# Grove_I2C_FM_Receiver_v1_0.net
KiCad netlist of a schematic drawn in EAGLE
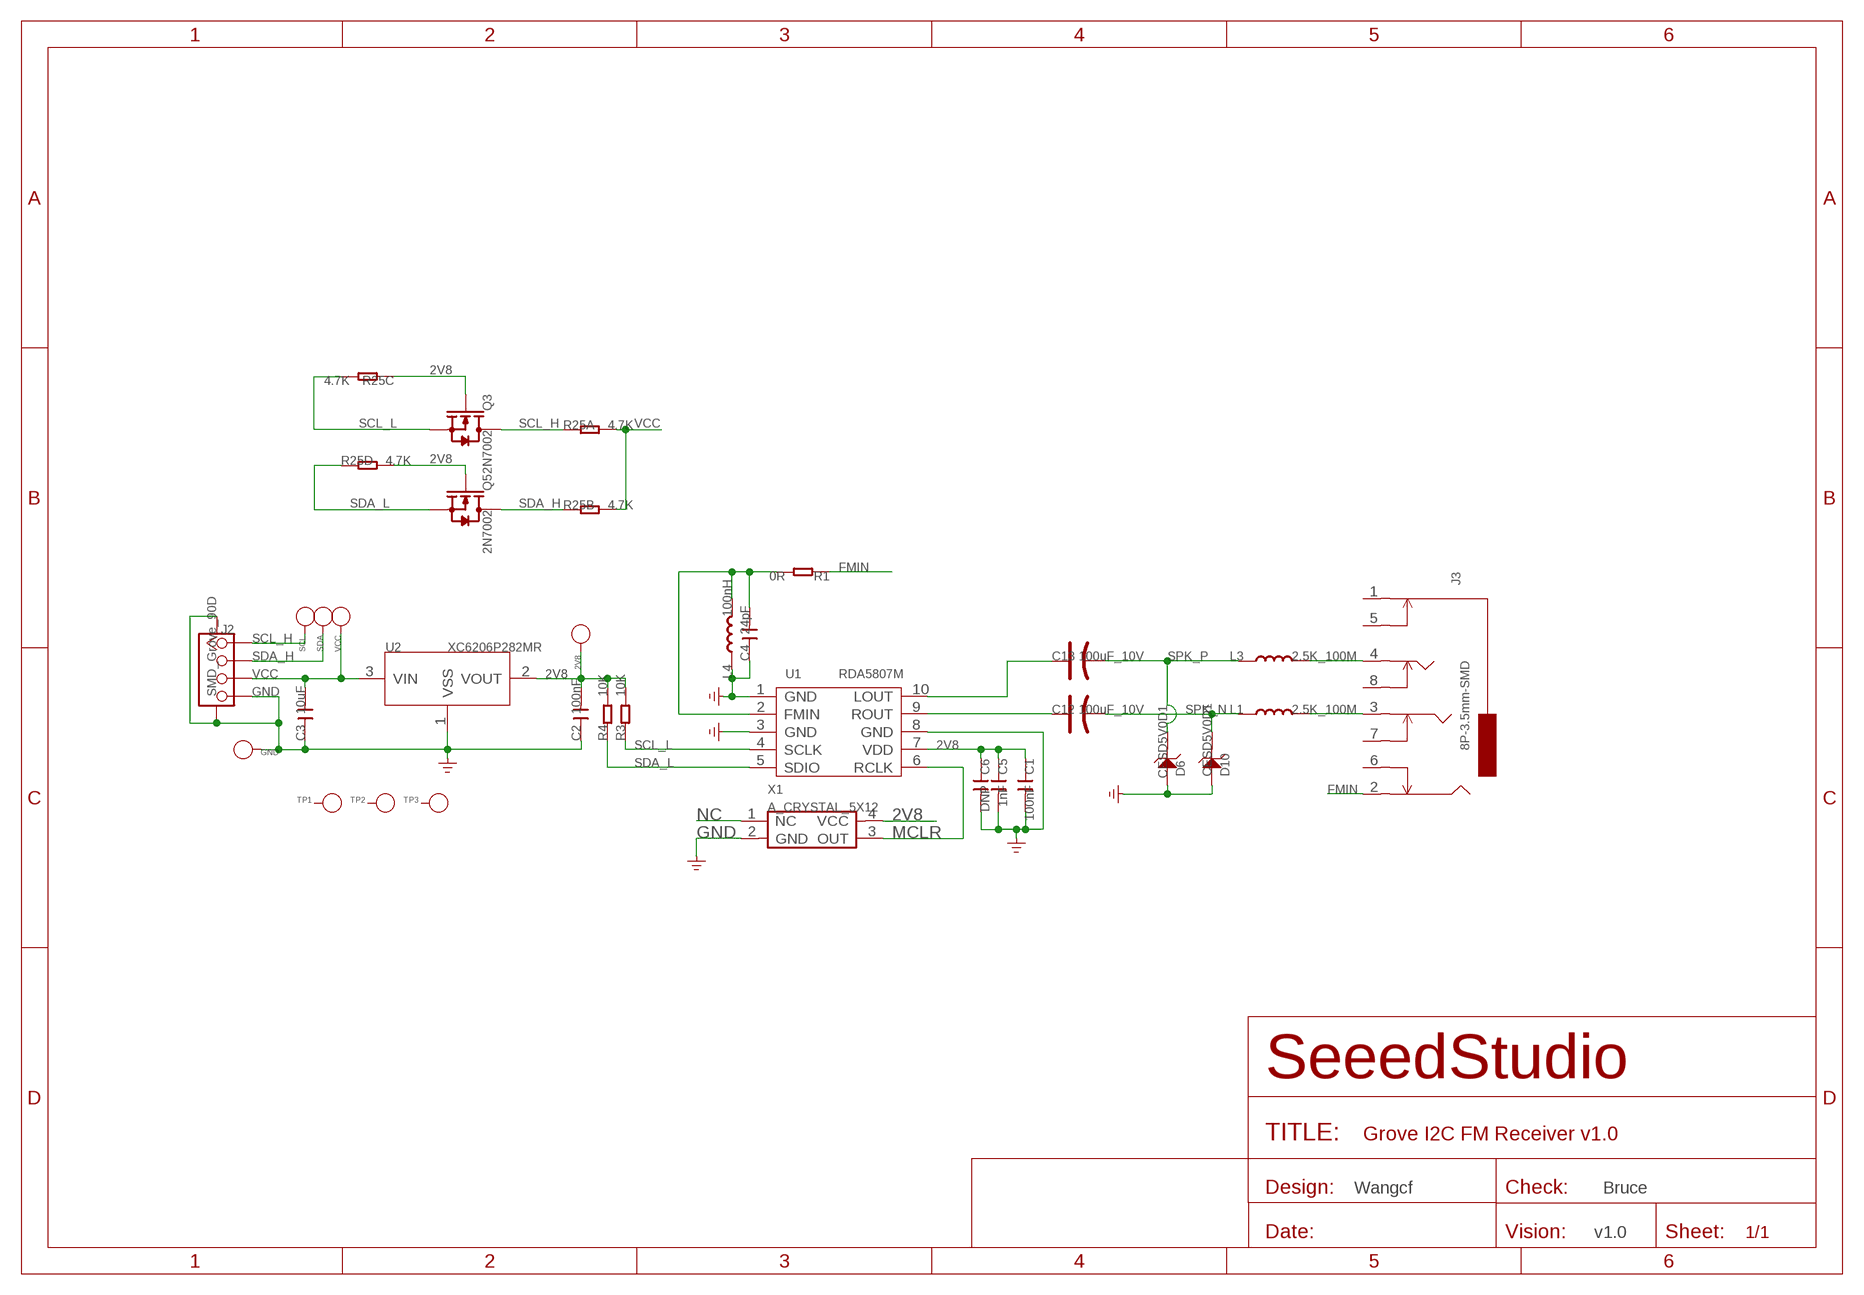
[diagram p0: schematic, sheet 1]

(export (version "E")
  (design (tool "Eeschema 10.0.6"))
  (components
    (comp (ref "2V8")
      (value "PAD-TEST-POINT'4545'")
      (footprint "eagle-import:TP_4545")
      (fields (field (name "PARTNO") "DNP"))
      (libsource (lib "eagle-import") (part "PAD-TEST-POINT'4545'"))
    )
    (comp (ref "C1")
      (value "100nF")
      (footprint "eagle-import:C0603")
      (libsource (lib "eagle-import") (part "C-0603"))
    )
    (comp (ref "C2")
      (value "100nF")
      (footprint "eagle-import:C0603")
      (libsource (lib "eagle-import") (part "C-0603"))
    )
    (comp (ref "C3")
      (value "10uF")
      (footprint "eagle-import:C0805")
      (libsource (lib "eagle-import") (part "C-0805"))
    )
    (comp (ref "C4")
      (value "24pF")
      (footprint "eagle-import:C0603")
      (libsource (lib "eagle-import") (part "C-0603"))
    )
    (comp (ref "C5")
      (value "1nF")
      (footprint "eagle-import:C0603")
      (libsource (lib "eagle-import") (part "C-0603"))
    )
    (comp (ref "C6")
      (value "DNP")
      (footprint "eagle-import:C0603")
      (libsource (lib "eagle-import") (part "C-0603"))
    )
    (comp (ref "C12")
      (value "100uF_10V")
      (footprint "eagle-import:AVX-B")
      (libsource (lib "eagle-import") (part "CAP-AVX-B"))
    )
    (comp (ref "C13")
      (value "100uF_10V")
      (footprint "eagle-import:AVX-B")
      (libsource (lib "eagle-import") (part "CAP-AVX-B"))
    )
    (comp (ref "D6")
      (value "CESD5V0D1")
      (footprint "eagle-import:SOD123-2.7X1.6")
      (libsource (lib "eagle-import") (part "D-ESD"))
    )
    (comp (ref "D10")
      (value "CESD5V0D1")
      (footprint "eagle-import:SOD123-2.7X1.6")
      (libsource (lib "eagle-import") (part "D-ESD"))
    )
    (comp (ref "GND")
      (value "PAD-TEST-POINT'4545'")
      (footprint "eagle-import:TP_4545")
      (fields (field (name "PARTNO") "DNP"))
      (libsource (lib "eagle-import") (part "PAD-TEST-POINT'4545'"))
    )
    (comp (ref "J2")
      (value "SMD_Grove_90D")
      (footprint "eagle-import:4P-SMD-2.0")
      (libsource (lib "eagle-import") (part "TWIG-4P-2.0-SMD-FEMALE-REINFORCE'DD'"))
    )
    (comp (ref "J3")
      (value "8P-3.5mm-SMD")
      (footprint "eagle-import:8P-3.5-SMD")
      (libsource (lib "eagle-import") (part "AUDIO-8P'PJ-3536-L6S'"))
    )
    (comp (ref "L1")
      (value "2.5K_100M")
      (footprint "eagle-import:L0603")
      (libsource (lib "eagle-import") (part "L'0603'"))
    )
    (comp (ref "L3")
      (value "2.5K_100M")
      (footprint "eagle-import:L0603")
      (libsource (lib "eagle-import") (part "L'0603'"))
    )
    (comp (ref "L4")
      (value "100nH")
      (footprint "eagle-import:L0603")
      (libsource (lib "eagle-import") (part "L'0603'"))
    )
    (comp (ref "Q3")
      (value "2N7002")
      (footprint "eagle-import:SOT23")
      (libsource (lib "eagle-import") (part "MOSFET-N'SOT23'"))
    )
    (comp (ref "Q5")
      (value "2N7002")
      (footprint "eagle-import:SOT23")
      (libsource (lib "eagle-import") (part "MOSFET-N'SOT23'"))
    )
    (comp (ref "R1")
      (value "0R")
      (footprint "eagle-import:R0603")
      (libsource (lib "eagle-import") (part "R-0603"))
    )
    (comp (ref "R3")
      (value "10K")
      (footprint "eagle-import:R0603")
      (libsource (lib "eagle-import") (part "R-0603"))
    )
    (comp (ref "R4")
      (value "10K")
      (footprint "eagle-import:R0603")
      (libsource (lib "eagle-import") (part "R-0603"))
    )
    (comp (ref "R25")
      (value "4.7K")
      (footprint "eagle-import:1206-8-3.3X2.4")
      (libsource (lib "eagle-import") (part "R-4R-1206"))
    )
    (comp (ref "SCL")
      (value "PAD-TEST-POINT'4545'")
      (footprint "eagle-import:TP_4545")
      (fields (field (name "PARTNO") "DNP"))
      (libsource (lib "eagle-import") (part "PAD-TEST-POINT'4545'"))
    )
    (comp (ref "SDA")
      (value "PAD-TEST-POINT'4545'")
      (footprint "eagle-import:TP_4545")
      (fields (field (name "PARTNO") "DNP"))
      (libsource (lib "eagle-import") (part "PAD-TEST-POINT'4545'"))
    )
    (comp (ref "TP1")
      (value "PAD-TEST-POINT'4545'")
      (footprint "eagle-import:TP_4545")
      (fields (field (name "PARTNO") "DNP"))
      (libsource (lib "eagle-import") (part "PAD-TEST-POINT'4545'"))
    )
    (comp (ref "TP2")
      (value "PAD-TEST-POINT'4545'")
      (footprint "eagle-import:TP_4545")
      (fields (field (name "PARTNO") "DNP"))
      (libsource (lib "eagle-import") (part "PAD-TEST-POINT'4545'"))
    )
    (comp (ref "TP3")
      (value "PAD-TEST-POINT'4545'")
      (footprint "eagle-import:TP_4545")
      (fields (field (name "PARTNO") "DNP"))
      (libsource (lib "eagle-import") (part "PAD-TEST-POINT'4545'"))
    )
    (comp (ref "U1")
      (value "RDA5807M")
      (footprint "eagle-import:MSOP10")
      (libsource (lib "eagle-import") (part "RDA5807M"))
    )
    (comp (ref "U2")
      (value "XC6206P282MR")
      (footprint "eagle-import:SOT23")
      (libsource (lib "eagle-import") (part "XC6206MR"))
    )
    (comp (ref "VCC")
      (value "PAD-TEST-POINT'4545'")
      (footprint "eagle-import:TP_4545")
      (fields (field (name "PARTNO") "DNP"))
      (libsource (lib "eagle-import") (part "PAD-TEST-POINT'4545'"))
    )
    (comp (ref "X1")
      (value "A_CRYSTAL_5X12")
      (footprint "eagle-import:4P_5X12")
      (libsource (lib "eagle-import") (part "A_CRYSTAL_5X12"))
    )
  )
  (nets
    (net (code "1") (name "/2V8") (class "Default")
      (node (ref "2V8") (pin "T") (pinfunction "T_T") (pintype "bidirectional"))
      (node (ref "C1") (pin "1") (pinfunction "1_1") (pintype "passive"))
      (node (ref "C2") (pin "2") (pinfunction "2_2") (pintype "passive"))
      (node (ref "C5") (pin "1") (pinfunction "1_1") (pintype "passive"))
      (node (ref "C6") (pin "1") (pinfunction "1_1") (pintype "passive"))
      (node (ref "Q3") (pin "1") (pinfunction "G_1") (pintype "passive"))
      (node (ref "Q5") (pin "1") (pinfunction "G_1") (pintype "passive"))
      (node (ref "R25") (pin "3") (pinfunction "1_3") (pintype "passive"))
      (node (ref "R25") (pin "5") (pinfunction "2_5") (pintype "passive"))
      (node (ref "R3") (pin "2") (pinfunction "2_2") (pintype "passive"))
      (node (ref "R4") (pin "2") (pinfunction "2_2") (pintype "passive"))
      (node (ref "U1") (pin "7") (pinfunction "VDD_7") (pintype "bidirectional"))
      (node (ref "U2") (pin "2") (pinfunction "VOUT_2") (pintype "output"))
      (node (ref "X1") (pin "4") (pinfunction "VCC_4") (pintype "bidirectional"))
    )
    (net (code "2") (name "/FMIN") (class "Default")
      (node (ref "J3") (pin "2") (pinfunction "2_2") (pintype "bidirectional"))
      (node (ref "R1") (pin "1") (pinfunction "1_1") (pintype "passive"))
    )
    (net (code "3") (name "/MCLR") (class "Default")
      (node (ref "U1") (pin "6") (pinfunction "RCLK_6") (pintype "bidirectional"))
      (node (ref "X1") (pin "3") (pinfunction "OUT_3") (pintype "bidirectional"))
    )
    (net (code "4") (name "/NC") (class "Default")
      (node (ref "X1") (pin "1") (pinfunction "NC_1") (pintype "bidirectional"))
    )
    (net (code "5") (name "/SCL_H") (class "Default")
      (node (ref "J2") (pin "1") (pinfunction "1_1") (pintype "bidirectional"))
      (node (ref "Q3") (pin "3") (pinfunction "D_3") (pintype "passive"))
      (node (ref "R25") (pin "1") (pinfunction "1_1") (pintype "passive"))
      (node (ref "SCL") (pin "T") (pinfunction "T_T") (pintype "bidirectional"))
    )
    (net (code "6") (name "/SCL_L") (class "Default")
      (node (ref "Q3") (pin "2") (pinfunction "S_2") (pintype "passive"))
      (node (ref "R25") (pin "6") (pinfunction "2_6") (pintype "passive"))
      (node (ref "R3") (pin "1") (pinfunction "1_1") (pintype "passive"))
      (node (ref "U1") (pin "4") (pinfunction "SCLK_4") (pintype "bidirectional"))
    )
    (net (code "7") (name "/SDA_H") (class "Default")
      (node (ref "J2") (pin "2") (pinfunction "2_2") (pintype "bidirectional"))
      (node (ref "Q5") (pin "3") (pinfunction "D_3") (pintype "passive"))
      (node (ref "R25") (pin "2") (pinfunction "1_2") (pintype "passive"))
      (node (ref "SDA") (pin "T") (pinfunction "T_T") (pintype "bidirectional"))
    )
    (net (code "8") (name "/SDA_L") (class "Default")
      (node (ref "Q5") (pin "2") (pinfunction "S_2") (pintype "passive"))
      (node (ref "R25") (pin "4") (pinfunction "1_4") (pintype "passive"))
      (node (ref "R4") (pin "1") (pinfunction "1_1") (pintype "passive"))
      (node (ref "U1") (pin "5") (pinfunction "SDIO_5") (pintype "bidirectional"))
    )
    (net (code "9") (name "/SPK_N") (class "Default")
      (node (ref "C12") (pin "-") (pinfunction "-_-") (pintype "passive"))
      (node (ref "D10") (pin "2") (pinfunction "2_2") (pintype "bidirectional"))
      (node (ref "L1") (pin "1") (pinfunction "1_1") (pintype "passive"))
    )
    (net (code "10") (name "/SPK_P") (class "Default")
      (node (ref "C13") (pin "-") (pinfunction "-_-") (pintype "passive"))
      (node (ref "D6") (pin "2") (pinfunction "2_2") (pintype "bidirectional"))
      (node (ref "L3") (pin "1") (pinfunction "1_1") (pintype "passive"))
    )
    (net (code "11") (name "/VCC") (class "Default")
      (node (ref "C3") (pin "2") (pinfunction "2_2") (pintype "passive"))
      (node (ref "J2") (pin "3") (pinfunction "3_3") (pintype "bidirectional"))
      (node (ref "R25") (pin "7") (pinfunction "2_7") (pintype "passive"))
      (node (ref "R25") (pin "8") (pinfunction "2_8") (pintype "passive"))
      (node (ref "U2") (pin "3") (pinfunction "VIN_3") (pintype "input"))
      (node (ref "VCC") (pin "T") (pinfunction "T_T") (pintype "bidirectional"))
    )
    (net (code "12") (name "GND_POWER") (class "Default")
      (node (ref "C1") (pin "2") (pinfunction "2_2") (pintype "passive"))
      (node (ref "C2") (pin "1") (pinfunction "1_1") (pintype "passive"))
      (node (ref "C3") (pin "1") (pinfunction "1_1") (pintype "passive"))
      (node (ref "C4") (pin "1") (pinfunction "1_1") (pintype "passive"))
      (node (ref "C5") (pin "2") (pinfunction "2_2") (pintype "passive"))
      (node (ref "C6") (pin "2") (pinfunction "2_2") (pintype "passive"))
      (node (ref "D10") (pin "1") (pinfunction "1_1") (pintype "bidirectional"))
      (node (ref "D6") (pin "1") (pinfunction "1_1") (pintype "bidirectional"))
      (node (ref "GND") (pin "T") (pinfunction "T_T") (pintype "bidirectional"))
      (node (ref "J2") (pin "4") (pinfunction "4_4") (pintype "bidirectional"))
      (node (ref "J2") (pin "SS1") (pinfunction "SS1_SS1") (pintype "bidirectional"))
      (node (ref "J2") (pin "SS2") (pinfunction "SS2_SS2") (pintype "bidirectional"))
      (node (ref "L4") (pin "1") (pinfunction "1_1") (pintype "passive"))
      (node (ref "U1") (pin "1") (pinfunction "GND_1") (pintype "bidirectional"))
      (node (ref "U1") (pin "3") (pinfunction "GND_3") (pintype "bidirectional"))
      (node (ref "U1") (pin "8") (pinfunction "GND_8") (pintype "bidirectional"))
      (node (ref "U2") (pin "1") (pinfunction "VSS_1") (pintype "power_in"))
      (node (ref "X1") (pin "2") (pinfunction "GND_2") (pintype "bidirectional"))
    )
    (net (code "13") (name "Net-(J3-Pad3)") (class "Default")
      (node (ref "J3") (pin "3") (pinfunction "3_3") (pintype "bidirectional"))
      (node (ref "L1") (pin "2") (pinfunction "2_2") (pintype "passive"))
    )
    (net (code "14") (name "Net-(J3-Pad4)") (class "Default")
      (node (ref "J3") (pin "4") (pinfunction "4_4") (pintype "bidirectional"))
      (node (ref "L3") (pin "2") (pinfunction "2_2") (pintype "passive"))
    )
    (net (code "15") (name "Net-(U1-FMIN)") (class "Default")
      (node (ref "C4") (pin "2") (pinfunction "2_2") (pintype "passive"))
      (node (ref "L4") (pin "2") (pinfunction "2_2") (pintype "passive"))
      (node (ref "R1") (pin "2") (pinfunction "2_2") (pintype "passive"))
      (node (ref "U1") (pin "2") (pinfunction "FMIN_2") (pintype "bidirectional"))
    )
    (net (code "16") (name "Net-(U1-LOUT)") (class "Default")
      (node (ref "C13") (pin "+") (pinfunction "+_+") (pintype "passive"))
      (node (ref "U1") (pin "10") (pinfunction "LOUT_10") (pintype "bidirectional"))
    )
    (net (code "17") (name "Net-(U1-ROUT)") (class "Default")
      (node (ref "C12") (pin "+") (pinfunction "+_+") (pintype "passive"))
      (node (ref "U1") (pin "9") (pinfunction "ROUT_9") (pintype "bidirectional"))
    )
    (net (code "18") (name "unconnected-(J3-Pad1)") (class "Default")
      (node (ref "J3") (pin "1") (pinfunction "1_1") (pintype "bidirectional"))
    )
    (net (code "19") (name "unconnected-(J3-Pad5)") (class "Default")
      (node (ref "J3") (pin "5") (pinfunction "5_5") (pintype "bidirectional"))
    )
    (net (code "20") (name "unconnected-(J3-Pad6)") (class "Default")
      (node (ref "J3") (pin "6") (pinfunction "6_6") (pintype "bidirectional"))
    )
    (net (code "21") (name "unconnected-(J3-Pad7)") (class "Default")
      (node (ref "J3") (pin "7") (pinfunction "7_7") (pintype "bidirectional"))
    )
    (net (code "22") (name "unconnected-(J3-Pad8)") (class "Default")
      (node (ref "J3") (pin "8") (pinfunction "8_8") (pintype "bidirectional"))
    )
    (net (code "23") (name "unconnected-(TP1-PadT)") (class "Default")
      (node (ref "TP1") (pin "T") (pinfunction "T_T") (pintype "bidirectional"))
    )
    (net (code "24") (name "unconnected-(TP2-PadT)") (class "Default")
      (node (ref "TP2") (pin "T") (pinfunction "T_T") (pintype "bidirectional"))
    )
    (net (code "25") (name "unconnected-(TP3-PadT)") (class "Default")
      (node (ref "TP3") (pin "T") (pinfunction "T_T") (pintype "bidirectional"))
    )
  )
)
